# design.net
KiCad netlist of a schematic drawn in EasyEDA
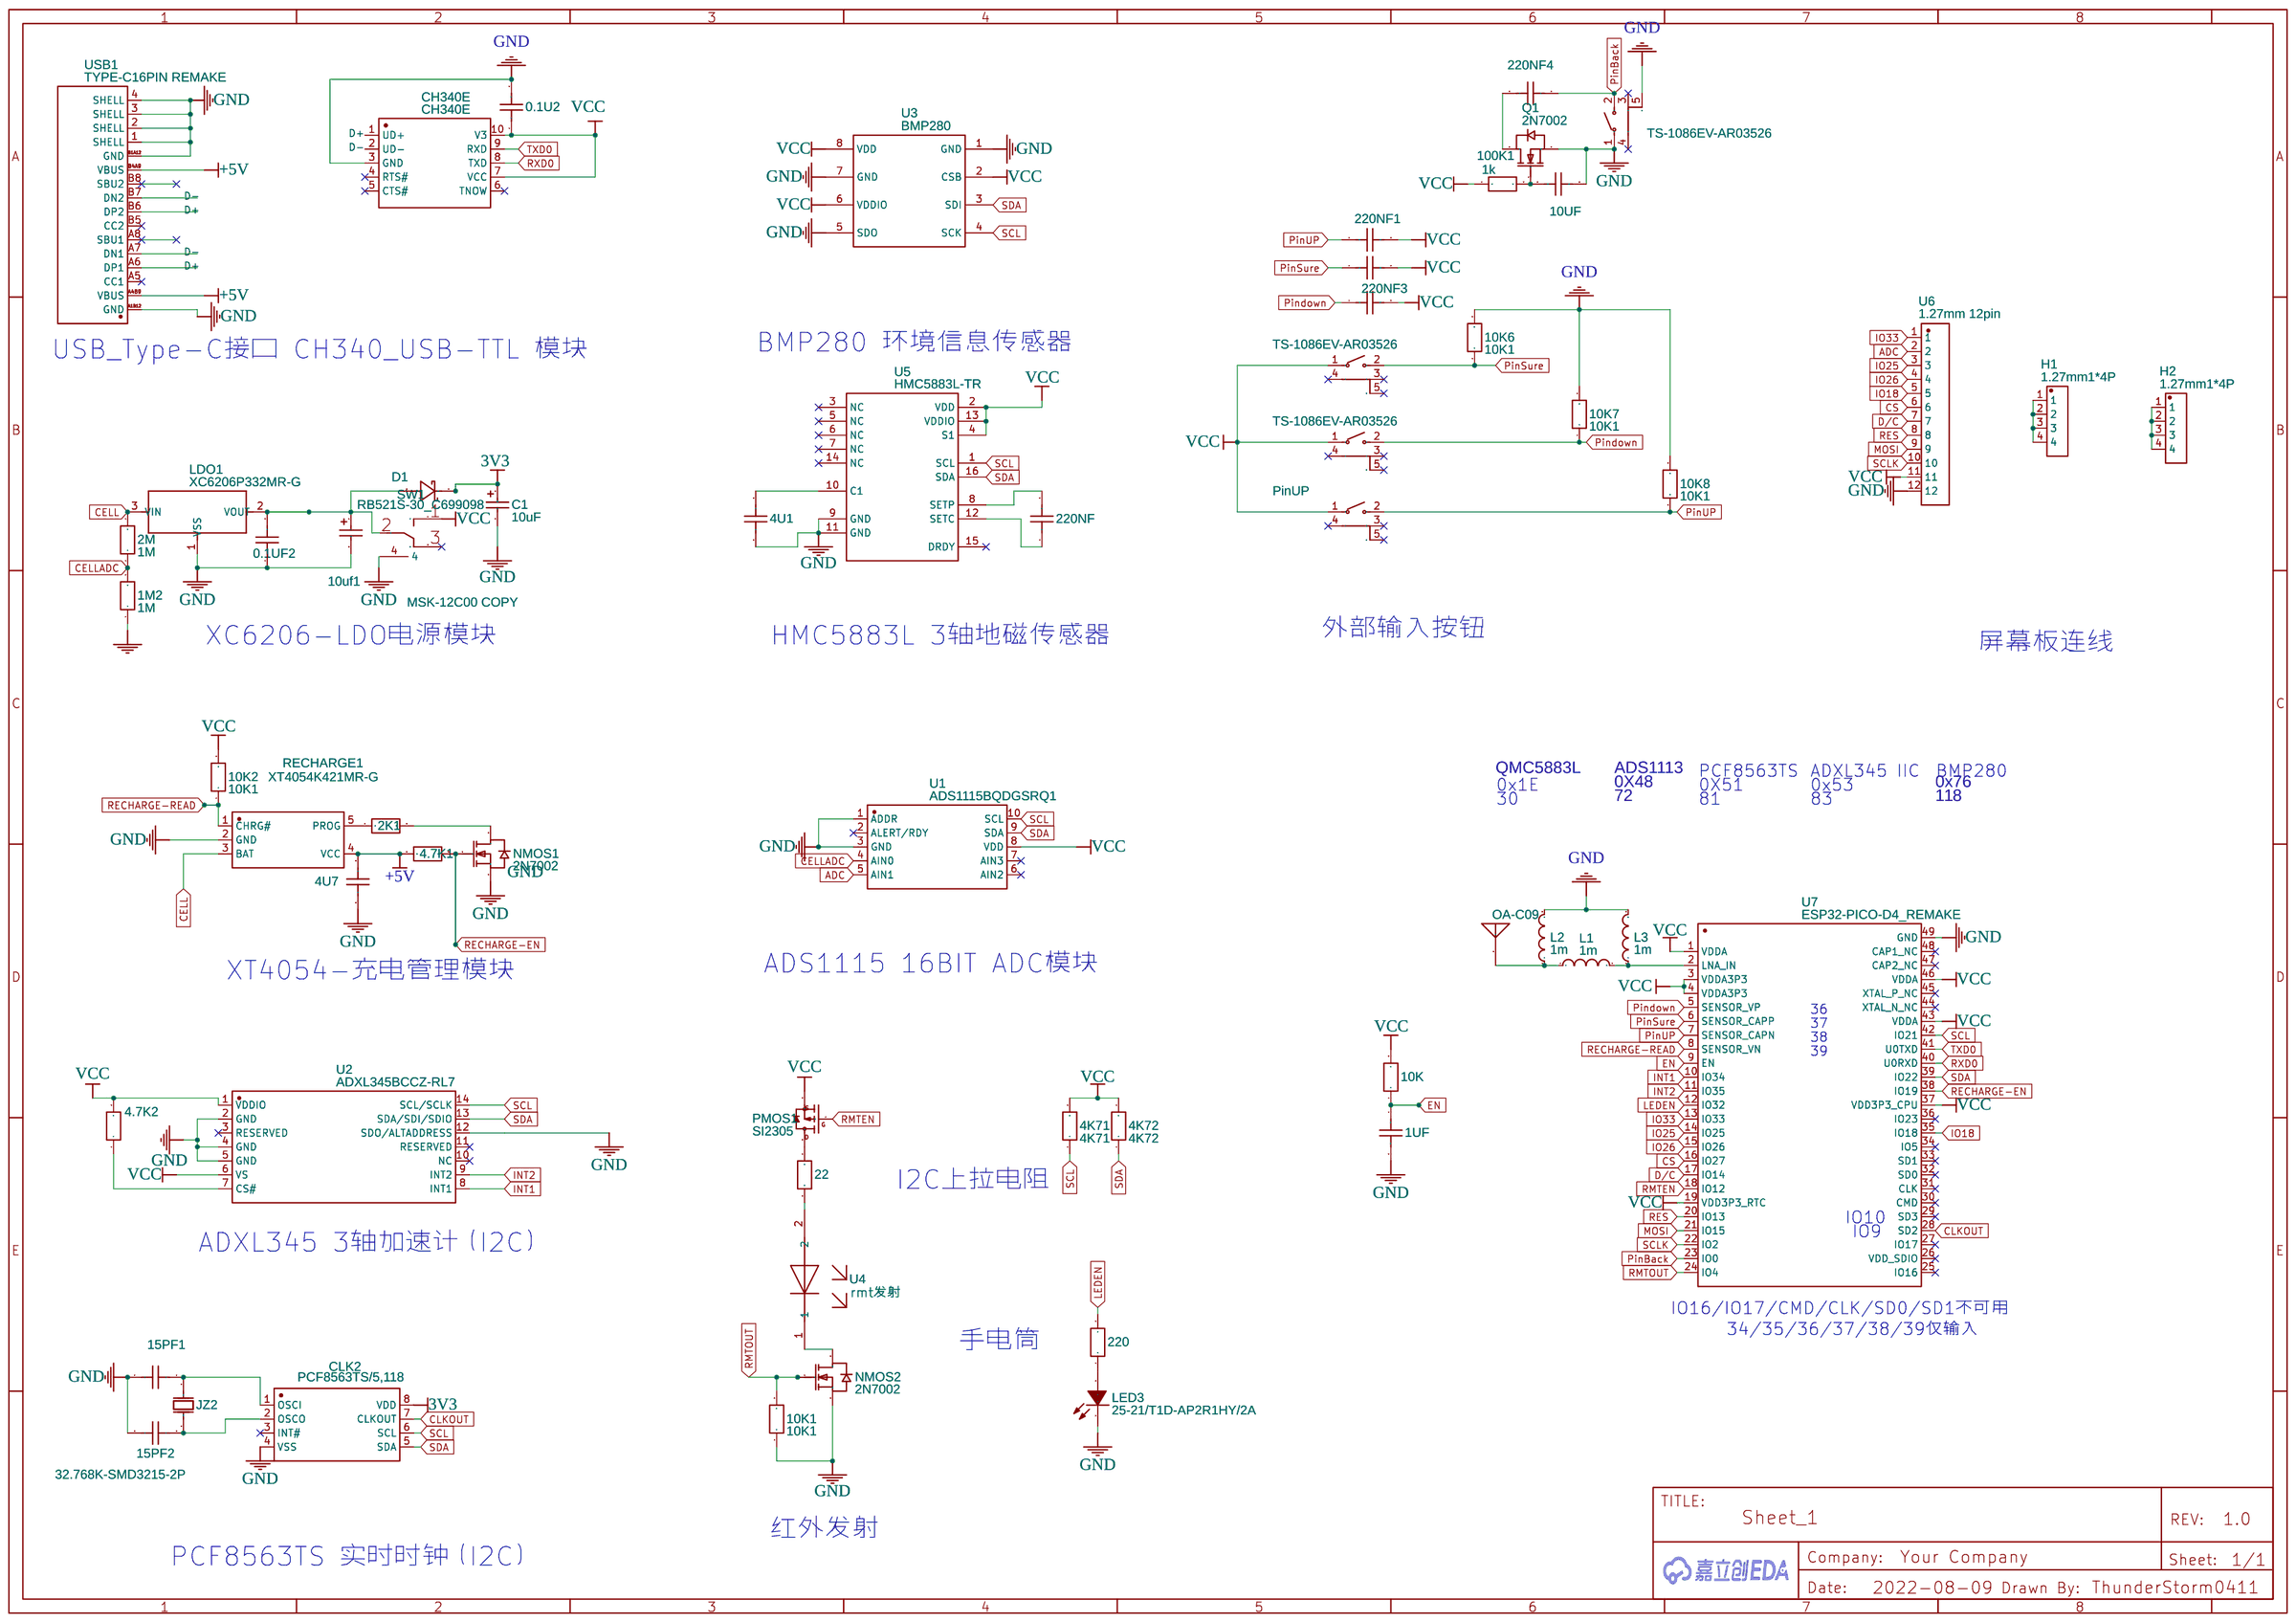
[diagram p0: schematic sheet]

(export (version "E")
  (design (tool "Eeschema 10.0.6"))
  (components
    (comp (ref "0.1U2") (value "0.1u") (libsource (lib "") (part "C_0603_US_4")))
    (comp (ref "0.1UF2") (value "0.1u") (libsource (lib "") (part "C_0603_US_7")))
    (comp (ref "1") (value "OA-C09") (libsource (lib "") (part "OA-C09")))
    (comp (ref "1M2") (value "1M") (libsource (lib "") (part "R_0603_EU_8")))
    (comp (ref "1UF")
      (value "1uF")
      (fields
        (field (name "BOM_Manufacturer Part") "TMK107BJ105KA-T")
        (field (name "BOM_Supplier Part") "C92828")
      )
      (libsource (lib "") (part "TMK107BJ105KA-T"))
    )
    (comp (ref "2K1") (value "2k1") (libsource (lib "") (part "R_0603_EU_7")))
    (comp (ref "2M") (value "1M") (libsource (lib "") (part "R_0603_EU_3")))
    (comp (ref "4.7K1") (value "4.7K") (libsource (lib "") (part "R_0603_EU_4")))
    (comp (ref "4.7K2")
      (value "4.7K")
      (fields
        (field (name "BOM_Manufacturer Part") "SY0603DD30KP")
        (field (name "BOM_Supplier Part") "C2763744")
      )
      (libsource (lib "") (part "SY0603DD30KP"))
    )
    (comp (ref "4K71") (value "4K71") (libsource (lib "") (part "R_0603_EU_1")))
    (comp (ref "4K72") (value "4K72") (libsource (lib "") (part "R_0603_EU_1")))
    (comp (ref "4U1") (value "0.1u") (libsource (lib "") (part "C_0603_US_2")))
    (comp (ref "4U7") (value "4.7uf") (libsource (lib "") (part "C_0603_US_2")))
    (comp (ref "10K")
      (value "10kΩ")
      (fields
        (field (name "BOM_Manufacturer Part") "PCAN0603E49R9BST5")
        (field (name "BOM_Supplier Part") "C2073666")
      )
      (libsource (lib "") (part "PCAN0603E49R9BST5"))
    )
    (comp (ref "10K1") (value "10K1") (libsource (lib "") (part "R_0603_EU_5")))
    (comp (ref "10K2") (value "10K1") (libsource (lib "") (part "R_0603_EU_5")))
    (comp (ref "10K6") (value "10K1") (libsource (lib "") (part "R_0603_EU_5")))
    (comp (ref "10K7") (value "10K1") (libsource (lib "") (part "R_0603_EU_5")))
    (comp (ref "10K8") (value "10K1") (libsource (lib "") (part "R_0603_EU_5")))
    (comp (ref "10UF") (value "0.1u") (libsource (lib "") (part "C_0603_US_6")))
    (comp (ref "15PF1") (value "15PF") (libsource (lib "") (part "C_0603_US_3")))
    (comp (ref "15PF2") (value "15PF2") (libsource (lib "") (part "C_0603_US_3")))
    (comp (ref "22") (value "1001") (libsource (lib "") (part "R_0603_EU")))
    (comp (ref "100K1") (value "1k") (libsource (lib "") (part "R_0603_EU_2")))
    (comp (ref "220") (value "10K2") (libsource (lib "") (part "R_0603_EU_6")))
    (comp (ref "220NF") (value "0.1u") (libsource (lib "") (part "C_0603_US_5")))
    (comp (ref "220NF1") (value "0.1u") (libsource (lib "") (part "C_0603_US_1")))
    (comp (ref "220NF2") (value "0.1u") (libsource (lib "") (part "C_0603_US_1")))
    (comp (ref "220NF3") (value "0.1u") (libsource (lib "") (part "C_0603_US_1")))
    (comp (ref "220NF4") (value "0.1u") (libsource (lib "") (part "C_0603_US")))
    (comp (ref "BACK1")
      (value "TS-1086EV-AR03526")
      (fields (field (name "BOM_Supplier Part") "C720474"))
      (libsource (lib "") (part "TS-1086EV-AR03526_1"))
    )
    (comp (ref "C1")
      (value "10uF")
      (fields
        (field (name "BOM_Manufacturer Part") "TAJA106K016RNJ")
        (field (name "BOM_Supplier Part") "C7171")
      )
      (libsource (lib "") (part "TAJA106K016RNJ"))
    )
    (comp (ref "C5")
      (value "10uf1")
      (fields
        (field (name "BOM_Manufacturer Part") "TAJA106K016RNJ")
        (field (name "BOM_Supplier Part") "C7171")
      )
      (libsource (lib "") (part "TAJA106K016RNJ"))
    )
    (comp (ref "CH340E")
      (value "CH340E")
      (fields (field (name "BOM_Supplier Part") "C99652"))
      (libsource (lib "") (part "CH340E"))
    )
    (comp (ref "CLK2")
      (value "PCF8563TS/5,118")
      (fields (field (name "BOM_Supplier Part") "C27397"))
      (libsource (lib "") (part "PCF8563TS/5,118"))
    )
    (comp (ref "D1")
      (value "RB521S-30_C699098")
      (fields (field (name "BOM_Manufacturer Part") "RB521S-30") (field (name "BOM_Supplier Part") "C699098"))
      (libsource (lib "") (part "RB521S-30_C699098"))
    )
    (comp (ref "DOWN1")
      (value "TS-1086EV-AR03526")
      (fields (field (name "BOM_Supplier Part") "C720474"))
      (libsource (lib "") (part "TS-1086EV-AR03526"))
    )
    (comp (ref "H1")
      (value "1.27mm1*4P")
      (fields
        (field (name "BOM_Manufacturer Part") "1.27mm1*12P Straight Headers  Pins")
        (field (name "BOM_Supplier Part") "C28953")
      )
      (libsource (lib "") (part "1.27mm1*4P"))
    )
    (comp (ref "H2")
      (value "1.27mm1*4P")
      (fields
        (field (name "BOM_Manufacturer Part") "1.27mm1*12P Straight Headers  Pins")
        (field (name "BOM_Supplier Part") "C28953")
      )
      (libsource (lib "") (part "1.27mm1*4P"))
    )
    (comp (ref "JZ2")
      (value "32.768K-SMD3215-2P")
      (fields
        (field (name "BOM_Manufacturer Part") "32.768k-SMD3215-2P")
        (field (name "BOM_Supplier Part") "C9900005513")
      )
      (libsource (lib "") (part "32.768K-SMD3215-2P"))
    )
    (comp (ref "L1") (value "1m") (libsource (lib "") (part "L0603_US_1")))
    (comp (ref "L2") (value "1m") (libsource (lib "") (part "L0603_US")))
    (comp (ref "L3") (value "1m") (libsource (lib "") (part "L0603_US")))
    (comp (ref "LDO1") (value "XC6206P332MR-G") (libsource (lib "") (part "XC6206P332MR-G")))
    (comp (ref "LED3")
      (value "25-21/T1D-AP2R1HY/2A")
      (fields (field (name "BOM_Supplier Part") "C83915"))
      (libsource (lib "") (part "25-21/T1D-AP2R1HY/2A"))
    )
    (comp (ref "NMOS1")
      (value "2N7002")
      (fields (field (name "BOM_Manufacturer Part") "2N7002,215") (field (name "BOM_Supplier Part") "C65189"))
      (libsource (lib "") (part "2N7002_1"))
    )
    (comp (ref "NMOS2")
      (value "2N7002")
      (fields (field (name "BOM_Manufacturer Part") "2N7002,215") (field (name "BOM_Supplier Part") "C65189"))
      (libsource (lib "") (part "2N7002_1"))
    )
    (comp (ref "PMOS1")
      (value "SI2305")
      (fields (field (name "BOM_Supplier Part") "C181088"))
      (libsource (lib "") (part "SI2305"))
    )
    (comp (ref "Q1")
      (value "2N7002")
      (fields (field (name "BOM_Manufacturer Part") "2N7002,215") (field (name "BOM_Supplier Part") "C65189"))
      (libsource (lib "") (part "2N7002"))
    )
    (comp (ref "RECHARGE1")
      (value "XT4054K421MR-G")
      (fields (field (name "BOM_Supplier Part") "C141405"))
      (libsource (lib "") (part "XT4054K421MR-G"))
    )
    (comp (ref "SURE1")
      (value "TS-1086EV-AR03526")
      (fields (field (name "BOM_Supplier Part") "C720474"))
      (libsource (lib "") (part "TS-1086EV-AR03526_2"))
    )
    (comp (ref "SW1") (value "MSK-12C00 COPY") (libsource (lib "") (part "MSK-12C00 COPY")))
    (comp (ref "U1")
      (value "ADS1115BQDGSRQ1")
      (fields (field (name "BOM_Supplier Part") "C2868291"))
      (libsource (lib "") (part "ADS1115BQDGSRQ1"))
    )
    (comp (ref "U2")
      (value "ADXL345BCCZ-RL7")
      (fields (field (name "BOM_Supplier Part") "C9667"))
      (libsource (lib "") (part "ADXL345BCCZ-RL7"))
    )
    (comp (ref "U3")
      (value "BMP280")
      (fields (field (name "BOM_Supplier Part") "C83291"))
      (libsource (lib "") (part "BMP280"))
    )
    (comp (ref "U4") (value "rmt发射") (libsource (lib "") (part "rmt发射")))
    (comp (ref "U5")
      (value "HMC5883L-TR")
      (fields (field (name "BOM_Supplier Part") "C15640"))
      (libsource (lib "") (part "HMC5883L-TR"))
    )
    (comp (ref "U6") (value "1.27mm 12pin") (libsource (lib "") (part "1.27mm 12pin")))
    (comp (ref "U7")
      (value "ESP32-PICO-D4_REMAKE")
      (fields
        (field (name "BOM_Manufacturer Part") "ESP32-PICO-D4")
        (field (name "BOM_Supplier Part") "C193707")
      )
      (libsource (lib "") (part "ESP32-PICO-D4_REMAKE"))
    )
    (comp (ref "UP1")
      (value "PinUP")
      (fields
        (field (name "BOM_Manufacturer Part") "TS-1086EV-AR03526")
        (field (name "BOM_Supplier Part") "C720474")
      )
      (libsource (lib "") (part "TS-1086EV-AR03526_3"))
    )
    (comp (ref "USB1")
      (value "TYPE-C16PIN REMAKE")
      (fields
        (field (name "BOM_Manufacturer Part") "TYPE-C16PIN")
        (field (name "BOM_Supplier Part") "C393939")
      )
      (libsource (lib "") (part "TYPE-C16PIN REMAKE"))
    )
  )
  (nets
    (net (code "1") (name "+5V") (class "Default")
      (node (ref "4.7K1") (pin "1") (pinfunction "1_1") (pintype "unspecified"))
      (node (ref "4U7") (pin "2") (pinfunction "2_2") (pintype "unspecified"))
      (node (ref "RECHARGE1") (pin "4") (pinfunction "VCC_4") (pintype "unspecified"))
      (node (ref "USB1") (pin "A4B9") (pinfunction "VBUS_A4B9") (pintype "unspecified"))
      (node (ref "USB1") (pin "B4A9") (pinfunction "VBUS_B4A9") (pintype "unspecified"))
    )
    (net (code "2") (name "/D+") (class "Default")
      (node (ref "CH340E") (pin "1") (pinfunction "UD+_1") (pintype "unspecified"))
      (node (ref "USB1") (pin "A6") (pinfunction "DP1_A6") (pintype "unspecified"))
      (node (ref "USB1") (pin "B6") (pinfunction "DP2_B6") (pintype "unspecified"))
    )
    (net (code "3") (name "/D-") (class "Default")
      (node (ref "CH340E") (pin "2") (pinfunction "UD-_2") (pintype "unspecified"))
      (node (ref "USB1") (pin "A7") (pinfunction "DN1_A7") (pintype "unspecified"))
      (node (ref "USB1") (pin "B7") (pinfunction "DN2_B7") (pintype "unspecified"))
    )
    (net (code "4") (name "3V3") (class "Default")
      (node (ref "C1") (pin "1") (pinfunction "1_1") (pintype "input"))
      (node (ref "CLK2") (pin "8") (pinfunction "VDD_8") (pintype "unspecified"))
      (node (ref "D1") (pin "1") (pinfunction "K_1") (pintype "unspecified"))
    )
    (net (code "5") (name "ADC") (class "Default")
      (node (ref "U1") (pin "5") (pinfunction "AIN1_5") (pintype "unspecified"))
      (node (ref "U6") (pin "2") (pinfunction "2_2") (pintype "unspecified"))
    )
    (net (code "6") (name "CELL") (class "Default")
      (node (ref "2M") (pin "2") (pinfunction "2_2") (pintype "unspecified"))
      (node (ref "LDO1") (pin "3") (pinfunction "VIN_3") (pintype "input"))
      (node (ref "RECHARGE1") (pin "3") (pinfunction "BAT_3") (pintype "unspecified"))
    )
    (net (code "7") (name "CELLADC") (class "Default")
      (node (ref "1M2") (pin "2") (pinfunction "2_2") (pintype "unspecified"))
      (node (ref "2M") (pin "1") (pinfunction "1_1") (pintype "unspecified"))
      (node (ref "U1") (pin "4") (pinfunction "AIN0_4") (pintype "unspecified"))
    )
    (net (code "8") (name "CLKOUT") (class "Default")
      (node (ref "CLK2") (pin "7") (pinfunction "CLKOUT_7") (pintype "unspecified"))
      (node (ref "U7") (pin "28") (pinfunction "SD2_28") (pintype "unspecified"))
    )
    (net (code "9") (name "CS") (class "Default")
      (node (ref "U6") (pin "6") (pinfunction "6_6") (pintype "unspecified"))
      (node (ref "U7") (pin "16") (pinfunction "IO27_16") (pintype "unspecified"))
    )
    (net (code "10") (name "D{slash}C") (class "Default")
      (node (ref "U6") (pin "7") (pinfunction "7_7") (pintype "unspecified"))
      (node (ref "U7") (pin "17") (pinfunction "IO14_17") (pintype "unspecified"))
    )
    (net (code "11") (name "EN") (class "Default")
      (node (ref "10K") (pin "1") (pinfunction "1_1") (pintype "unspecified"))
      (node (ref "1UF") (pin "1") (pinfunction "1_1") (pintype "unspecified"))
      (node (ref "U7") (pin "9") (pinfunction "EN_9") (pintype "unspecified"))
    )
    (net (code "12") (name "GND") (class "Default")
      (node (ref "0.1U2") (pin "2") (pinfunction "2_2") (pintype "unspecified"))
      (node (ref "0.1UF2") (pin "1") (pinfunction "1_1") (pintype "unspecified"))
      (node (ref "10K1") (pin "1") (pinfunction "1_1") (pintype "unspecified"))
      (node (ref "10K6") (pin "2") (pinfunction "2_2") (pintype "unspecified"))
      (node (ref "10K7") (pin "2") (pinfunction "2_2") (pintype "unspecified"))
      (node (ref "10K8") (pin "2") (pinfunction "2_2") (pintype "unspecified"))
      (node (ref "10UF") (pin "2") (pinfunction "2_2") (pintype "unspecified"))
      (node (ref "15PF1") (pin "1") (pinfunction "1_1") (pintype "unspecified"))
      (node (ref "15PF2") (pin "1") (pinfunction "1_1") (pintype "unspecified"))
      (node (ref "1M2") (pin "1") (pinfunction "1_1") (pintype "unspecified"))
      (node (ref "1UF") (pin "2") (pinfunction "2_2") (pintype "unspecified"))
      (node (ref "4U1") (pin "1") (pinfunction "1_1") (pintype "unspecified"))
      (node (ref "4U7") (pin "1") (pinfunction "1_1") (pintype "unspecified"))
      (node (ref "BACK1") (pin "1") (pinfunction "1_1") (pintype "unspecified"))
      (node (ref "BACK1") (pin "5") (pinfunction "5_5") (pintype "unspecified"))
      (node (ref "C1") (pin "2") (pinfunction "2_2") (pintype "input"))
      (node (ref "C5") (pin "2") (pinfunction "2_2") (pintype "input"))
      (node (ref "CH340E") (pin "3") (pinfunction "GND_3") (pintype "unspecified"))
      (node (ref "CLK2") (pin "4") (pinfunction "VSS_4") (pintype "unspecified"))
      (node (ref "L2") (pin "2") (pinfunction "2_2") (pintype "unspecified"))
      (node (ref "L3") (pin "2") (pinfunction "2_2") (pintype "unspecified"))
      (node (ref "LDO1") (pin "1") (pinfunction "VSS_1") (pintype "unspecified"))
      (node (ref "LED3") (pin "2") (pinfunction "K_2") (pintype "unspecified"))
      (node (ref "NMOS1") (pin "2") (pinfunction "S_2") (pintype "unspecified"))
      (node (ref "NMOS2") (pin "2") (pinfunction "S_2") (pintype "unspecified"))
      (node (ref "Q1") (pin "2") (pinfunction "S_2") (pintype "unspecified"))
      (node (ref "RECHARGE1") (pin "2") (pinfunction "GND_2") (pintype "unspecified"))
      (node (ref "SW1") (pin "4") (pinfunction "4_4") (pintype "unspecified"))
      (node (ref "U1") (pin "1") (pinfunction "ADDR_1") (pintype "unspecified"))
      (node (ref "U1") (pin "3") (pinfunction "GND_3") (pintype "unspecified"))
      (node (ref "U2") (pin "12") (pinfunction "SDO/ALTADDRESS_12") (pintype "unspecified"))
      (node (ref "U2") (pin "2") (pinfunction "GND_2") (pintype "unspecified"))
      (node (ref "U2") (pin "4") (pinfunction "GND_4") (pintype "unspecified"))
      (node (ref "U2") (pin "5") (pinfunction "GND_5") (pintype "unspecified"))
      (node (ref "U3") (pin "1") (pinfunction "GND_1") (pintype "unspecified"))
      (node (ref "U3") (pin "5") (pinfunction "SDO_5") (pintype "unspecified"))
      (node (ref "U3") (pin "7") (pinfunction "GND_7") (pintype "unspecified"))
      (node (ref "U5") (pin "11") (pinfunction "GND_11") (pintype "unspecified"))
      (node (ref "U5") (pin "9") (pinfunction "GND_9") (pintype "unspecified"))
      (node (ref "U6") (pin "12") (pinfunction "12_12") (pintype "unspecified"))
      (node (ref "U7") (pin "49") (pinfunction "GND_49") (pintype "unspecified"))
      (node (ref "USB1") (pin "1") (pinfunction "SHELL_1") (pintype "unspecified"))
      (node (ref "USB1") (pin "2") (pinfunction "SHELL_2") (pintype "unspecified"))
      (node (ref "USB1") (pin "3") (pinfunction "SHELL_3") (pintype "unspecified"))
      (node (ref "USB1") (pin "4") (pinfunction "SHELL_4") (pintype "unspecified"))
      (node (ref "USB1") (pin "A1B12") (pinfunction "GND_A1B12") (pintype "unspecified"))
      (node (ref "USB1") (pin "B1A12") (pinfunction "GND_B1A12") (pintype "unspecified"))
    )
    (net (code "13") (name "INT1") (class "Default")
      (node (ref "U2") (pin "8") (pinfunction "INT1_8") (pintype "unspecified"))
      (node (ref "U7") (pin "10") (pinfunction "IO34_10") (pintype "unspecified"))
    )
    (net (code "14") (name "INT2") (class "Default")
      (node (ref "U2") (pin "9") (pinfunction "INT2_9") (pintype "unspecified"))
      (node (ref "U7") (pin "11") (pinfunction "IO35_11") (pintype "unspecified"))
    )
    (net (code "15") (name "IO18") (class "Default")
      (node (ref "U6") (pin "5") (pinfunction "5_5") (pintype "unspecified"))
      (node (ref "U7") (pin "35") (pinfunction "IO18_35") (pintype "unspecified"))
    )
    (net (code "16") (name "IO25") (class "Default")
      (node (ref "U6") (pin "3") (pinfunction "3_3") (pintype "unspecified"))
      (node (ref "U7") (pin "14") (pinfunction "IO25_14") (pintype "unspecified"))
    )
    (net (code "17") (name "IO26") (class "Default")
      (node (ref "U6") (pin "4") (pinfunction "4_4") (pintype "unspecified"))
      (node (ref "U7") (pin "15") (pinfunction "IO26_15") (pintype "unspecified"))
    )
    (net (code "18") (name "IO33") (class "Default")
      (node (ref "U6") (pin "1") (pinfunction "1_1") (pintype "unspecified"))
      (node (ref "U7") (pin "13") (pinfunction "IO33_13") (pintype "unspecified"))
    )
    (net (code "19") (name "LEDEN") (class "Default")
      (node (ref "220") (pin "2") (pinfunction "2_2") (pintype "unspecified"))
      (node (ref "U7") (pin "12") (pinfunction "IO32_12") (pintype "unspecified"))
    )
    (net (code "20") (name "MOSI") (class "Default")
      (node (ref "U6") (pin "9") (pinfunction "9_9") (pintype "unspecified"))
      (node (ref "U7") (pin "21") (pinfunction "IO15_21") (pintype "unspecified"))
    )
    (net (code "21") (name "Net-(1-Pad1)") (class "Default")
      (node (ref "1") (pin "1") (pinfunction "1_1") (pintype "unspecified"))
      (node (ref "L1") (pin "1") (pinfunction "1_1") (pintype "unspecified"))
      (node (ref "L2") (pin "1") (pinfunction "1_1") (pintype "unspecified"))
    )
    (net (code "22") (name "Net-(22-Pad2)") (class "Default")
      (node (ref "22") (pin "2") (pinfunction "2_2") (pintype "unspecified"))
      (node (ref "U4") (pin "2") (pinfunction "2_2") (pintype "unspecified"))
    )
    (net (code "23") (name "Net-(CLK2-OSCI)") (class "Default")
      (node (ref "15PF1") (pin "2") (pinfunction "2_2") (pintype "unspecified"))
      (node (ref "CLK2") (pin "1") (pinfunction "OSCI_1") (pintype "unspecified"))
      (node (ref "JZ2") (pin "2") (pinfunction "OSC2_2") (pintype "input"))
    )
    (net (code "24") (name "Net-(CLK2-OSCO)") (class "Default")
      (node (ref "15PF2") (pin "2") (pinfunction "2_2") (pintype "unspecified"))
      (node (ref "CLK2") (pin "2") (pinfunction "OSCO_2") (pintype "unspecified"))
      (node (ref "JZ2") (pin "1") (pinfunction "OSC1_1") (pintype "input"))
    )
    (net (code "25") (name "Net-(D1-A)") (class "Default")
      (node (ref "0.1UF2") (pin "2") (pinfunction "2_2") (pintype "unspecified"))
      (node (ref "C5") (pin "1") (pinfunction "1_1") (pintype "input"))
      (node (ref "D1") (pin "2") (pinfunction "A_2") (pintype "unspecified"))
      (node (ref "LDO1") (pin "2") (pinfunction "VOUT_2") (pintype "output"))
      (node (ref "SW1") (pin "2") (pinfunction "2_2") (pintype "unspecified"))
    )
    (net (code "26") (name "Net-(H1-Pad1)") (class "Default")
      (node (ref "H1") (pin "1") (pinfunction "1_1") (pintype "unspecified"))
      (node (ref "H1") (pin "2") (pinfunction "2_2") (pintype "unspecified"))
      (node (ref "H1") (pin "3") (pinfunction "3_3") (pintype "unspecified"))
      (node (ref "H1") (pin "4") (pinfunction "4_4") (pintype "unspecified"))
    )
    (net (code "27") (name "Net-(H2-Pad1)") (class "Default")
      (node (ref "H2") (pin "1") (pinfunction "1_1") (pintype "unspecified"))
      (node (ref "H2") (pin "2") (pinfunction "2_2") (pintype "unspecified"))
      (node (ref "H2") (pin "3") (pinfunction "3_3") (pintype "unspecified"))
      (node (ref "H2") (pin "4") (pinfunction "4_4") (pintype "unspecified"))
    )
    (net (code "28") (name "Net-(LED3-A)") (class "Default")
      (node (ref "220") (pin "1") (pinfunction "1_1") (pintype "unspecified"))
      (node (ref "LED3") (pin "1") (pinfunction "A_1") (pintype "unspecified"))
    )
    (net (code "29") (name "Net-(NMOS1-D)") (class "Default")
      (node (ref "2K1") (pin "2") (pinfunction "2_2") (pintype "unspecified"))
      (node (ref "NMOS1") (pin "3") (pinfunction "D_3") (pintype "unspecified"))
    )
    (net (code "30") (name "Net-(NMOS2-D)") (class "Default")
      (node (ref "NMOS2") (pin "3") (pinfunction "D_3") (pintype "unspecified"))
      (node (ref "U4") (pin "1") (pinfunction "1_1") (pintype "unspecified"))
    )
    (net (code "31") (name "Net-(PMOS1-D)") (class "Default")
      (node (ref "22") (pin "1") (pinfunction "1_1") (pintype "unspecified"))
      (node (ref "PMOS1") (pin "3") (pinfunction "D_3") (pintype "unspecified"))
    )
    (net (code "32") (name "Net-(Q1-D)") (class "Default")
      (node (ref "220NF4") (pin "2") (pinfunction "2_2") (pintype "unspecified"))
      (node (ref "Q1") (pin "3") (pinfunction "D_3") (pintype "unspecified"))
    )
    (net (code "33") (name "Net-(Q1-G)") (class "Default")
      (node (ref "100K1") (pin "2") (pinfunction "2_2") (pintype "unspecified"))
      (node (ref "10UF") (pin "1") (pinfunction "1_1") (pintype "unspecified"))
      (node (ref "Q1") (pin "1") (pinfunction "G_1") (pintype "unspecified"))
    )
    (net (code "34") (name "Net-(RECHARGE1-PROG)") (class "Default")
      (node (ref "2K1") (pin "1") (pinfunction "1_1") (pintype "unspecified"))
      (node (ref "RECHARGE1") (pin "5") (pinfunction "PROG_5") (pintype "unspecified"))
    )
    (net (code "35") (name "Net-(U2-CS#)") (class "Default")
      (node (ref "4.7K2") (pin "1") (pinfunction "1_1") (pintype "unspecified"))
      (node (ref "U2") (pin "7") (pinfunction "CS#_7") (pintype "unspecified"))
    )
    (net (code "36") (name "Net-(U5-C1)") (class "Default")
      (node (ref "4U1") (pin "2") (pinfunction "2_2") (pintype "unspecified"))
      (node (ref "U5") (pin "10") (pinfunction "C1_10") (pintype "unspecified"))
    )
    (net (code "37") (name "Net-(U5-SETC)") (class "Default")
      (node (ref "220NF") (pin "1") (pinfunction "1_1") (pintype "unspecified"))
      (node (ref "U5") (pin "12") (pinfunction "SETC_12") (pintype "unspecified"))
    )
    (net (code "38") (name "Net-(U5-SETP)") (class "Default")
      (node (ref "220NF") (pin "2") (pinfunction "2_2") (pintype "unspecified"))
      (node (ref "U5") (pin "8") (pinfunction "SETP_8") (pintype "unspecified"))
    )
    (net (code "39") (name "Net-(U7-LNA_IN)") (class "Default")
      (node (ref "L1") (pin "2") (pinfunction "2_2") (pintype "unspecified"))
      (node (ref "L3") (pin "1") (pinfunction "1_1") (pintype "unspecified"))
      (node (ref "U7") (pin "2") (pinfunction "LNA_IN_2") (pintype "unspecified"))
    )
    (net (code "40") (name "PinBack") (class "Default")
      (node (ref "220NF4") (pin "1") (pinfunction "1_1") (pintype "unspecified"))
      (node (ref "BACK1") (pin "2") (pinfunction "2_2") (pintype "unspecified"))
      (node (ref "U7") (pin "23") (pinfunction "IO0_23") (pintype "unspecified"))
    )
    (net (code "41") (name "PinSure") (class "Default")
      (node (ref "10K6") (pin "1") (pinfunction "1_1") (pintype "unspecified"))
      (node (ref "220NF2") (pin "1") (pinfunction "1_1") (pintype "unspecified"))
      (node (ref "SURE1") (pin "2") (pinfunction "2_2") (pintype "unspecified"))
      (node (ref "U7") (pin "6") (pinfunction "SENSOR_CAPP_6") (pintype "unspecified"))
    )
    (net (code "42") (name "PinUP") (class "Default")
      (node (ref "10K8") (pin "1") (pinfunction "1_1") (pintype "unspecified"))
      (node (ref "220NF1") (pin "1") (pinfunction "1_1") (pintype "unspecified"))
      (node (ref "U7") (pin "7") (pinfunction "SENSOR_CAPN_7") (pintype "unspecified"))
      (node (ref "UP1") (pin "2") (pinfunction "2_2") (pintype "unspecified"))
    )
    (net (code "43") (name "Pindown") (class "Default")
      (node (ref "10K7") (pin "1") (pinfunction "1_1") (pintype "unspecified"))
      (node (ref "220NF3") (pin "1") (pinfunction "1_1") (pintype "unspecified"))
      (node (ref "DOWN1") (pin "2") (pinfunction "2_2") (pintype "unspecified"))
      (node (ref "U7") (pin "5") (pinfunction "SENSOR_VP_5") (pintype "unspecified"))
    )
    (net (code "44") (name "RECHARGE-EN") (class "Default")
      (node (ref "4.7K1") (pin "2") (pinfunction "2_2") (pintype "unspecified"))
      (node (ref "NMOS1") (pin "1") (pinfunction "G_1") (pintype "unspecified"))
      (node (ref "U7") (pin "38") (pinfunction "IO19_38") (pintype "unspecified"))
    )
    (net (code "45") (name "RECHARGE-READ") (class "Default")
      (node (ref "10K2") (pin "1") (pinfunction "1_1") (pintype "unspecified"))
      (node (ref "RECHARGE1") (pin "1") (pinfunction "CHRG#_1") (pintype "unspecified"))
      (node (ref "U7") (pin "8") (pinfunction "SENSOR_VN_8") (pintype "unspecified"))
    )
    (net (code "46") (name "RES") (class "Default")
      (node (ref "U6") (pin "8") (pinfunction "8_8") (pintype "unspecified"))
      (node (ref "U7") (pin "20") (pinfunction "IO13_20") (pintype "unspecified"))
    )
    (net (code "47") (name "RMTEN") (class "Default")
      (node (ref "PMOS1") (pin "1") (pinfunction "G_1") (pintype "unspecified"))
      (node (ref "U7") (pin "18") (pinfunction "IO12_18") (pintype "unspecified"))
    )
    (net (code "48") (name "RMTOUT") (class "Default")
      (node (ref "10K1") (pin "2") (pinfunction "2_2") (pintype "unspecified"))
      (node (ref "NMOS2") (pin "1") (pinfunction "G_1") (pintype "unspecified"))
      (node (ref "U7") (pin "24") (pinfunction "IO4_24") (pintype "unspecified"))
    )
    (net (code "49") (name "RXD0") (class "Default")
      (node (ref "CH340E") (pin "8") (pinfunction "TXD_8") (pintype "unspecified"))
      (node (ref "U7") (pin "40") (pinfunction "U0RXD_40") (pintype "unspecified"))
    )
    (net (code "50") (name "SCL") (class "Default")
      (node (ref "4K71") (pin "1") (pinfunction "1_1") (pintype "unspecified"))
      (node (ref "CLK2") (pin "6") (pinfunction "SCL_6") (pintype "unspecified"))
      (node (ref "U1") (pin "10") (pinfunction "SCL_10") (pintype "unspecified"))
      (node (ref "U2") (pin "14") (pinfunction "SCL/SCLK_14") (pintype "unspecified"))
      (node (ref "U3") (pin "4") (pinfunction "SCK_4") (pintype "unspecified"))
      (node (ref "U5") (pin "1") (pinfunction "SCL_1") (pintype "unspecified"))
      (node (ref "U7") (pin "42") (pinfunction "IO21_42") (pintype "unspecified"))
    )
    (net (code "51") (name "SCLK") (class "Default")
      (node (ref "U6") (pin "10") (pinfunction "10_10") (pintype "unspecified"))
      (node (ref "U7") (pin "22") (pinfunction "IO2_22") (pintype "unspecified"))
    )
    (net (code "52") (name "SDA") (class "Default")
      (node (ref "4K72") (pin "1") (pinfunction "1_1") (pintype "unspecified"))
      (node (ref "CLK2") (pin "5") (pinfunction "SDA_5") (pintype "unspecified"))
      (node (ref "U1") (pin "9") (pinfunction "SDA_9") (pintype "unspecified"))
      (node (ref "U2") (pin "13") (pinfunction "SDA/SDI/SDIO_13") (pintype "unspecified"))
      (node (ref "U3") (pin "3") (pinfunction "SDI_3") (pintype "unspecified"))
      (node (ref "U5") (pin "16") (pinfunction "SDA_16") (pintype "unspecified"))
      (node (ref "U7") (pin "39") (pinfunction "IO22_39") (pintype "unspecified"))
    )
    (net (code "53") (name "TXD0") (class "Default")
      (node (ref "CH340E") (pin "9") (pinfunction "RXD_9") (pintype "unspecified"))
      (node (ref "U7") (pin "41") (pinfunction "U0TXD_41") (pintype "unspecified"))
    )
    (net (code "54") (name "VCC") (class "Default")
      (node (ref "0.1U2") (pin "1") (pinfunction "1_1") (pintype "unspecified"))
      (node (ref "100K1") (pin "1") (pinfunction "1_1") (pintype "unspecified"))
      (node (ref "10K") (pin "2") (pinfunction "2_2") (pintype "unspecified"))
      (node (ref "10K2") (pin "2") (pinfunction "2_2") (pintype "unspecified"))
      (node (ref "220NF1") (pin "2") (pinfunction "2_2") (pintype "unspecified"))
      (node (ref "220NF2") (pin "2") (pinfunction "2_2") (pintype "unspecified"))
      (node (ref "220NF3") (pin "2") (pinfunction "2_2") (pintype "unspecified"))
      (node (ref "4.7K2") (pin "2") (pinfunction "2_2") (pintype "unspecified"))
      (node (ref "4K71") (pin "2") (pinfunction "2_2") (pintype "unspecified"))
      (node (ref "4K72") (pin "2") (pinfunction "2_2") (pintype "unspecified"))
      (node (ref "CH340E") (pin "10") (pinfunction "V3_10") (pintype "unspecified"))
      (node (ref "CH340E") (pin "7") (pinfunction "VCC_7") (pintype "unspecified"))
      (node (ref "DOWN1") (pin "1") (pinfunction "1_1") (pintype "unspecified"))
      (node (ref "PMOS1") (pin "2") (pinfunction "S_2") (pintype "unspecified"))
      (node (ref "SURE1") (pin "1") (pinfunction "1_1") (pintype "unspecified"))
      (node (ref "SW1") (pin "1") (pinfunction "1_1") (pintype "unspecified"))
      (node (ref "U1") (pin "8") (pinfunction "VDD_8") (pintype "unspecified"))
      (node (ref "U2") (pin "1") (pinfunction "VDDIO_1") (pintype "unspecified"))
      (node (ref "U2") (pin "6") (pinfunction "VS_6") (pintype "unspecified"))
      (node (ref "U3") (pin "2") (pinfunction "CSB_2") (pintype "unspecified"))
      (node (ref "U3") (pin "6") (pinfunction "VDDIO_6") (pintype "unspecified"))
      (node (ref "U3") (pin "8") (pinfunction "VDD_8") (pintype "unspecified"))
      (node (ref "U5") (pin "13") (pinfunction "VDDIO_13") (pintype "unspecified"))
      (node (ref "U5") (pin "2") (pinfunction "VDD_2") (pintype "unspecified"))
      (node (ref "U5") (pin "4") (pinfunction "S1_4") (pintype "unspecified"))
      (node (ref "U6") (pin "11") (pinfunction "11_11") (pintype "unspecified"))
      (node (ref "U7") (pin "1") (pinfunction "VDDA_1") (pintype "unspecified"))
      (node (ref "U7") (pin "19") (pinfunction "VDD3P3_RTC_19") (pintype "unspecified"))
      (node (ref "U7") (pin "3") (pinfunction "VDDA3P3_3") (pintype "unspecified"))
      (node (ref "U7") (pin "37") (pinfunction "VDD3P3_CPU_37") (pintype "unspecified"))
      (node (ref "U7") (pin "4") (pinfunction "VDDA3P3_4") (pintype "unspecified"))
      (node (ref "U7") (pin "43") (pinfunction "VDDA_43") (pintype "unspecified"))
      (node (ref "U7") (pin "46") (pinfunction "VDDA_46") (pintype "unspecified"))
      (node (ref "UP1") (pin "1") (pinfunction "1_1") (pintype "unspecified"))
    )
    (net (code "55") (name "unconnected-(BACK1-Pad3)") (class "Default")
      (node (ref "BACK1") (pin "3") (pinfunction "3_3") (pintype "unspecified+no_connect"))
    )
    (net (code "56") (name "unconnected-(BACK1-Pad4)") (class "Default")
      (node (ref "BACK1") (pin "4") (pinfunction "4_4") (pintype "unspecified+no_connect"))
    )
    (net (code "57") (name "unconnected-(CH340E-CTS#-Pad5)") (class "Default")
      (node (ref "CH340E") (pin "5") (pinfunction "CTS#_5") (pintype "unspecified+no_connect"))
    )
    (net (code "58") (name "unconnected-(CH340E-RTS#-Pad4)") (class "Default")
      (node (ref "CH340E") (pin "4") (pinfunction "RTS#_4") (pintype "unspecified+no_connect"))
    )
    (net (code "59") (name "unconnected-(CH340E-TNOW-Pad6)") (class "Default")
      (node (ref "CH340E") (pin "6") (pinfunction "TNOW_6") (pintype "unspecified+no_connect"))
    )
    (net (code "60") (name "unconnected-(CLK2-INT#-Pad3)") (class "Default")
      (node (ref "CLK2") (pin "3") (pinfunction "INT#_3") (pintype "unspecified+no_connect"))
    )
    (net (code "61") (name "unconnected-(DOWN1-Pad3)") (class "Default")
      (node (ref "DOWN1") (pin "3") (pinfunction "3_3") (pintype "unspecified+no_connect"))
    )
    (net (code "62") (name "unconnected-(DOWN1-Pad4)") (class "Default")
      (node (ref "DOWN1") (pin "4") (pinfunction "4_4") (pintype "unspecified+no_connect"))
    )
    (net (code "63") (name "unconnected-(DOWN1-Pad5)") (class "Default")
      (node (ref "DOWN1") (pin "5") (pinfunction "5_5") (pintype "unspecified+no_connect"))
    )
    (net (code "64") (name "unconnected-(SURE1-Pad3)") (class "Default")
      (node (ref "SURE1") (pin "3") (pinfunction "3_3") (pintype "unspecified+no_connect"))
    )
    (net (code "65") (name "unconnected-(SURE1-Pad4)") (class "Default")
      (node (ref "SURE1") (pin "4") (pinfunction "4_4") (pintype "unspecified+no_connect"))
    )
    (net (code "66") (name "unconnected-(SURE1-Pad5)") (class "Default")
      (node (ref "SURE1") (pin "5") (pinfunction "5_5") (pintype "unspecified+no_connect"))
    )
    (net (code "67") (name "unconnected-(SW1-Pad3)") (class "Default")
      (node (ref "SW1") (pin "3") (pinfunction "3_3") (pintype "unspecified+no_connect"))
    )
    (net (code "68") (name "unconnected-(U1-AIN2-Pad6)") (class "Default")
      (node (ref "U1") (pin "6") (pinfunction "AIN2_6") (pintype "unspecified+no_connect"))
    )
    (net (code "69") (name "unconnected-(U1-AIN3-Pad7)") (class "Default")
      (node (ref "U1") (pin "7") (pinfunction "AIN3_7") (pintype "unspecified+no_connect"))
    )
    (net (code "70") (name "unconnected-(U1-ALERT{slash}RDY-Pad2)") (class "Default")
      (node (ref "U1") (pin "2") (pinfunction "ALERT/RDY_2") (pintype "unspecified+no_connect"))
    )
    (net (code "71") (name "unconnected-(U2-NC-Pad10)") (class "Default")
      (node (ref "U2") (pin "10") (pinfunction "NC_10") (pintype "unspecified+no_connect"))
    )
    (net (code "72") (name "unconnected-(U2-RESERVED-Pad3)") (class "Default")
      (node (ref "U2") (pin "3") (pinfunction "RESERVED_3") (pintype "unspecified+no_connect"))
    )
    (net (code "73") (name "unconnected-(U2-RESERVED-Pad11)") (class "Default")
      (node (ref "U2") (pin "11") (pinfunction "RESERVED_11") (pintype "unspecified+no_connect"))
    )
    (net (code "74") (name "unconnected-(U5-DRDY-Pad15)") (class "Default")
      (node (ref "U5") (pin "15") (pinfunction "DRDY_15") (pintype "unspecified+no_connect"))
    )
    (net (code "75") (name "unconnected-(U5-NC-Pad3)") (class "Default")
      (node (ref "U5") (pin "3") (pinfunction "NC_3") (pintype "unspecified+no_connect"))
    )
    (net (code "76") (name "unconnected-(U5-NC-Pad5)") (class "Default")
      (node (ref "U5") (pin "5") (pinfunction "NC_5") (pintype "unspecified+no_connect"))
    )
    (net (code "77") (name "unconnected-(U5-NC-Pad6)") (class "Default")
      (node (ref "U5") (pin "6") (pinfunction "NC_6") (pintype "unspecified+no_connect"))
    )
    (net (code "78") (name "unconnected-(U5-NC-Pad7)") (class "Default")
      (node (ref "U5") (pin "7") (pinfunction "NC_7") (pintype "unspecified+no_connect"))
    )
    (net (code "79") (name "unconnected-(U5-NC-Pad14)") (class "Default")
      (node (ref "U5") (pin "14") (pinfunction "NC_14") (pintype "unspecified+no_connect"))
    )
    (net (code "80") (name "unconnected-(U7-CAP1_NC-Pad48)") (class "Default")
      (node (ref "U7") (pin "48") (pinfunction "CAP1_NC_48") (pintype "unspecified+no_connect"))
    )
    (net (code "81") (name "unconnected-(U7-CAP2_NC-Pad47)") (class "Default")
      (node (ref "U7") (pin "47") (pinfunction "CAP2_NC_47") (pintype "unspecified+no_connect"))
    )
    (net (code "82") (name "unconnected-(U7-CLK-Pad31)") (class "Default")
      (node (ref "U7") (pin "31") (pinfunction "CLK_31") (pintype "unspecified+no_connect"))
    )
    (net (code "83") (name "unconnected-(U7-CMD-Pad30)") (class "Default")
      (node (ref "U7") (pin "30") (pinfunction "CMD_30") (pintype "unspecified+no_connect"))
    )
    (net (code "84") (name "unconnected-(U7-IO5-Pad34)") (class "Default")
      (node (ref "U7") (pin "34") (pinfunction "IO5_34") (pintype "unspecified+no_connect"))
    )
    (net (code "85") (name "unconnected-(U7-IO16-Pad25)") (class "Default")
      (node (ref "U7") (pin "25") (pinfunction "IO16_25") (pintype "unspecified+no_connect"))
    )
    (net (code "86") (name "unconnected-(U7-IO17-Pad27)") (class "Default")
      (node (ref "U7") (pin "27") (pinfunction "IO17_27") (pintype "unspecified+no_connect"))
    )
    (net (code "87") (name "unconnected-(U7-IO23-Pad36)") (class "Default")
      (node (ref "U7") (pin "36") (pinfunction "IO23_36") (pintype "unspecified+no_connect"))
    )
    (net (code "88") (name "unconnected-(U7-SD0-Pad32)") (class "Default")
      (node (ref "U7") (pin "32") (pinfunction "SD0_32") (pintype "unspecified+no_connect"))
    )
    (net (code "89") (name "unconnected-(U7-SD1-Pad33)") (class "Default")
      (node (ref "U7") (pin "33") (pinfunction "SD1_33") (pintype "unspecified+no_connect"))
    )
    (net (code "90") (name "unconnected-(U7-SD3-Pad29)") (class "Default")
      (node (ref "U7") (pin "29") (pinfunction "SD3_29") (pintype "unspecified+no_connect"))
    )
    (net (code "91") (name "unconnected-(U7-VDD_SDIO-Pad26)") (class "Default")
      (node (ref "U7") (pin "26") (pinfunction "VDD_SDIO_26") (pintype "unspecified+no_connect"))
    )
    (net (code "92") (name "unconnected-(U7-XTAL_N_NC-Pad44)") (class "Default")
      (node (ref "U7") (pin "44") (pinfunction "XTAL_N_NC_44") (pintype "unspecified+no_connect"))
    )
    (net (code "93") (name "unconnected-(U7-XTAL_P_NC-Pad45)") (class "Default")
      (node (ref "U7") (pin "45") (pinfunction "XTAL_P_NC_45") (pintype "unspecified+no_connect"))
    )
    (net (code "94") (name "unconnected-(UP1-Pad3)") (class "Default")
      (node (ref "UP1") (pin "3") (pinfunction "3_3") (pintype "unspecified+no_connect"))
    )
    (net (code "95") (name "unconnected-(UP1-Pad4)") (class "Default")
      (node (ref "UP1") (pin "4") (pinfunction "4_4") (pintype "unspecified+no_connect"))
    )
    (net (code "96") (name "unconnected-(UP1-Pad5)") (class "Default")
      (node (ref "UP1") (pin "5") (pinfunction "5_5") (pintype "unspecified+no_connect"))
    )
    (net (code "97") (name "unconnected-(USB1-CC1-PadA5)") (class "Default")
      (node (ref "USB1") (pin "A5") (pinfunction "CC1_A5") (pintype "unspecified+no_connect"))
    )
    (net (code "98") (name "unconnected-(USB1-CC2-PadB5)") (class "Default")
      (node (ref "USB1") (pin "B5") (pinfunction "CC2_B5") (pintype "unspecified+no_connect"))
    )
    (net (code "99") (name "unconnected-(USB1-SBU1-PadA8)") (class "Default")
      (node (ref "USB1") (pin "A8") (pinfunction "SBU1_A8") (pintype "unspecified+no_connect"))
    )
    (net (code "100") (name "unconnected-(USB1-SBU2-PadB8)") (class "Default")
      (node (ref "USB1") (pin "B8") (pinfunction "SBU2_B8") (pintype "unspecified+no_connect"))
    )
  )
)
